# CallerID.net
KiCad netlist of a schematic drawn in Altium Designer
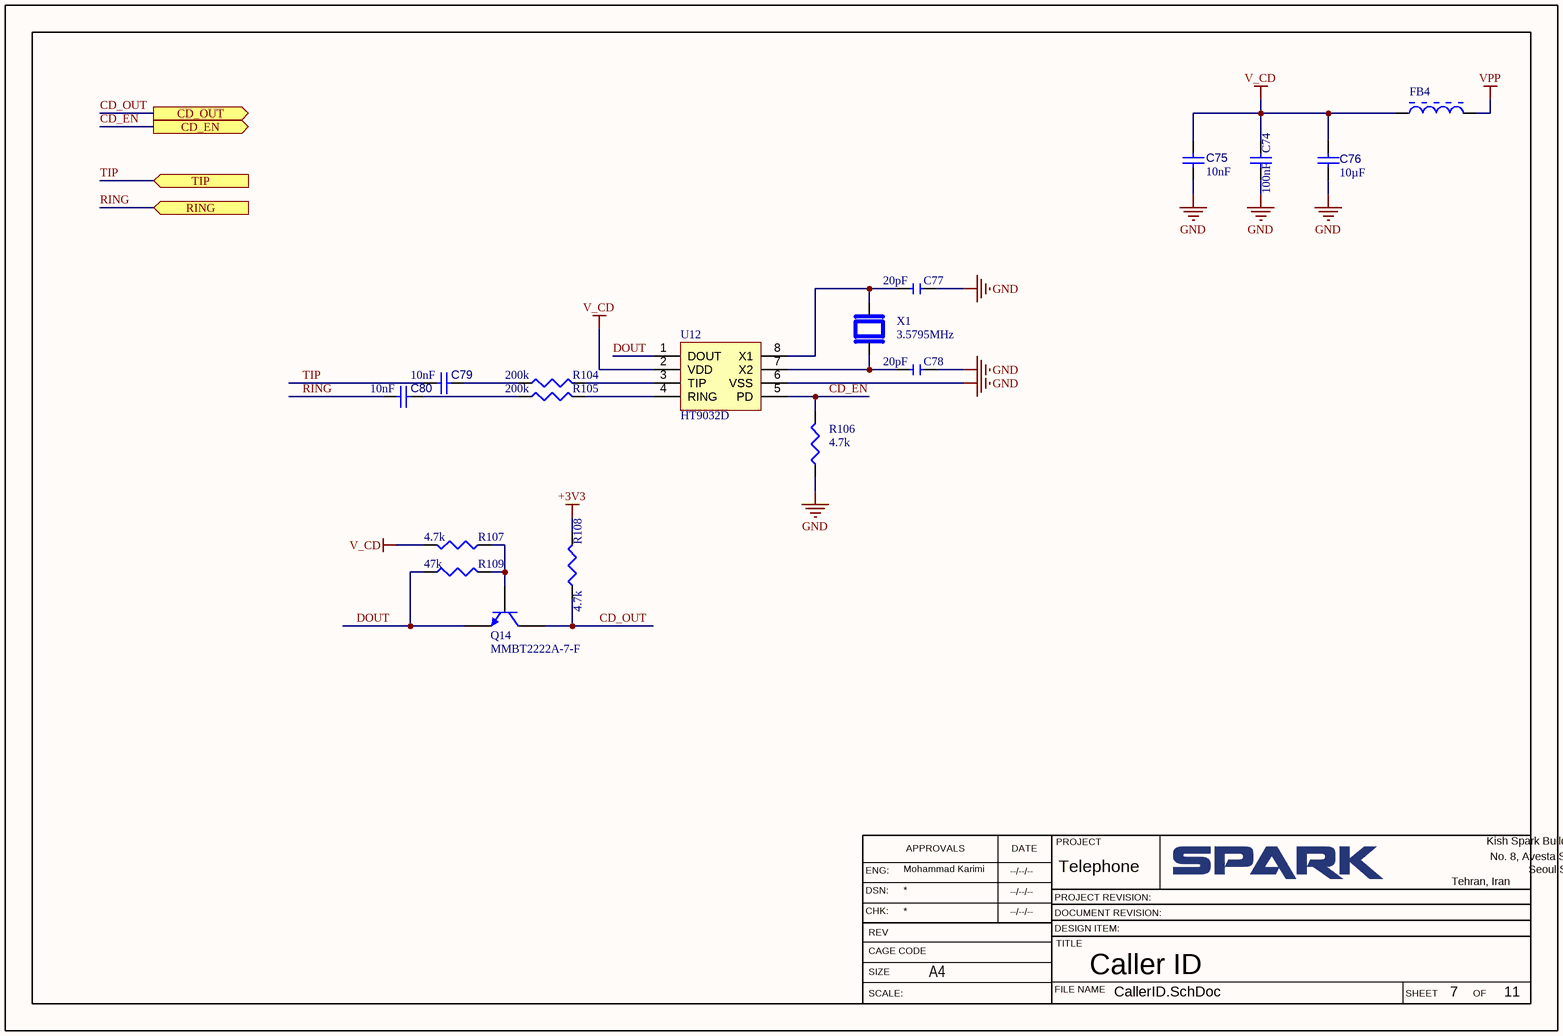
[diagram p0: CallerID.SchDoc]

(export (version "E")
  (design (tool "Eeschema 10.0.6"))
  (components
    (comp (ref "C74")
      (value "100nF")
      (footprint "C0603")
      (description "YAGEO - CC0603KRX7R8BB104 - CERAMIC CAPACITOR, 0.1UF, 25V, X7R, 10%, 0603, FULL REEL")
      (fields
        (field (name "TOLERANCE") "10%")
        (field (name "VOLTAGE") "25V")
        (field (name "SOURCE") "PTZLib.SchLib")
      )
      (libsource (lib "Kish Spark") (part "CAP-NP-2"))
    )
    (comp (ref "C75")
      (value "10nF")
      (footprint "C0603")
      (description "0603 10nF 50 V ±10 % Tolerance X7R Surface Mount Multilayer Ceramic Capacitor")
      (fields (field (name "TOLERANCE") "10%") (field (name "MANUFACTURER") "Kyocera AVX"))
      (libsource (lib "Kish Spark") (part "CAP-NP-2"))
    )
    (comp (ref "C76")
      (value "10µF")
      (footprint "0805")
      (description "Ceramic Capacitor, 10UF, 6.3V, X5R, 10%, 0805, Full Reel")
      (fields
        (field (name "MANUFACTURER") "KEMET")
        (field (name "MANUFACTURER PART NUMBER") "C0805C106K9PACTU")
      )
      (libsource (lib "Kish Spark") (part "CAP-NP-2"))
    )
    (comp (ref "C77")
      (value "20pF")
      (footprint "0805")
      (description "CAP CER 20PF 50V NPO 0805")
      (fields
        (field (name "MANUFACTURER") "Yageo")
        (field (name "MANUFACTURER PART NUMBER") "CC0805JRNPO9BN200")
      )
      (libsource (lib "Kish Spark") (part "CC0805JRNPO9BN200"))
    )
    (comp (ref "C78")
      (value "20pF")
      (footprint "0805")
      (description "CAP CER 20PF 50V NPO 0805")
      (fields
        (field (name "MANUFACTURER") "Yageo")
        (field (name "MANUFACTURER PART NUMBER") "CC0805JRNPO9BN200")
      )
      (libsource (lib "Kish Spark") (part "CC0805JRNPO9BN200"))
    )
    (comp (ref "C79")
      (value "10nF")
      (footprint "C0603")
      (description "0603 10nF 50 V ±10 % Tolerance X7R Surface Mount Multilayer Ceramic Capacitor")
      (fields (field (name "TOLERANCE") "10%") (field (name "MANUFACTURER") "Kyocera AVX"))
      (libsource (lib "Kish Spark") (part "CAP-NP-2"))
    )
    (comp (ref "C80")
      (value "10nF")
      (footprint "C0603")
      (description "0603 10nF 50 V ±10 % Tolerance X7R Surface Mount Multilayer Ceramic Capacitor")
      (fields (field (name "TOLERANCE") "10%") (field (name "MANUFACTURER") "Kyocera AVX"))
      (libsource (lib "Kish Spark") (part "CAP-NP-2"))
    )
    (comp (ref "FB4")
      (value "CMP-006-00051-1")
      (footprint "R0603")
      (description "Ferrite Beads 0603 60ohm")
      (fields (field (name "TOLERANCE") "25%") (field (name "SOURCE") "PTZLib.SchLib"))
      (libsource (lib "Kish Spark") (part "FerriteBead"))
    )
    (comp (ref "Q14")
      (value "MMBT2222A-7-F")
      (footprint "SOT23127P600-8N")
      (description "MMBT2222 Series NPN 350 mW 40 V 600 mA SMT Small Signal Transistor - SOT-23")
      (fields
        (field (name "MANUFACTURER") "Diodes")
        (field (name "VOLTAGE") "40V")
        (field (name "SOURCE") "PTZ.SCHLIB")
      )
      (libsource (lib "Kish Spark") (part "BJT-NPN-EBC-3"))
    )
    (comp (ref "R104")
      (value "200k")
      (footprint "0805")
      (description "Res Thick Film 0805 200K Ohm 1% 1/8W ±100ppm/°C Molded SMD Paper T/R")
      (fields
        (field (name "MANUFACTURER") "Yageo")
        (field (name "MANUFACTURER PART NUMBER") "RC0805FR-07200KL")
      )
      (libsource (lib "Kish Spark") (part "RC0805FR-1018KL (2)"))
    )
    (comp (ref "R105")
      (value "200k")
      (footprint "0805")
      (description "Res Thick Film 0805 200K Ohm 1% 1/8W ±100ppm/°C Molded SMD Paper T/R")
      (fields
        (field (name "MANUFACTURER") "Yageo")
        (field (name "MANUFACTURER PART NUMBER") "RC0805FR-07200KL")
      )
      (libsource (lib "Kish Spark") (part "RC0805FR-1018KL (2)"))
    )
    (comp (ref "R106")
      (value "4.7k")
      (footprint "R0603")
      (description "RES SMD 4.7K OHM 5% 1/10W 0603")
      (fields
        (field (name "TOLERANCE") "5%")
        (field (name "Comment") "KTR03EZPJ472")
        (field (name "SOURCE") "PTZLib.SchLib")
      )
      (libsource (lib "Kish Spark") (part "RN73R1JTTD3302F10"))
    )
    (comp (ref "R107")
      (value "4.7k")
      (footprint "R0603")
      (description "RES SMD 4.7K OHM 5% 1/10W 0603")
      (fields
        (field (name "TOLERANCE") "5%")
        (field (name "Comment") "KTR03EZPJ472")
        (field (name "SOURCE") "PTZLib.SchLib")
      )
      (libsource (lib "Kish Spark") (part "RN73R1JTTD3302F10"))
    )
    (comp (ref "R108")
      (value "4.7k")
      (footprint "R0603")
      (description "RES SMD 4.7K OHM 5% 1/10W 0603")
      (fields
        (field (name "TOLERANCE") "5%")
        (field (name "Comment") "KTR03EZPJ472")
        (field (name "SOURCE") "PTZLib.SchLib")
      )
      (libsource (lib "Kish Spark") (part "RN73R1JTTD3302F10"))
    )
    (comp (ref "R109")
      (value "47k")
      (footprint "0805")
      (description "High Precision-High Stability Chip Resistor Thin Film 0805 47kOhm 1% Paper T/R")
      (fields
        (field (name "MANUFACTURER") "Yageo")
        (field (name "MANUFACTURER PART NUMBER") "RT0805FRE0747KL")
      )
      (libsource (lib "Kish Spark") (part "RC0805FR-1018KL (2)"))
    )
    (comp (ref "U12")
      (value "HT9032D")
      (footprint "SSOIC8")
      (description "SOP-8 Telecommunication Interface ICs ROHS")
      (libsource (lib "Kish Spark") (part "HT9032D"))
    )
    (comp (ref "X1")
      (value "CMP-003-00038-1")
      (footprint "XTAL")
      (description "Crystal 3.579545MHz ±30ppm (Tol) ±50ppm (Stability) 18pF FUND 180Ohm 2-Pin HC-49/US SMD T/R")
      (fields
        (field (name "MANUFACTURER") "Abracon")
        (field (name "MANUFACTURER PART NUMBER") "ABLS-3.579545MHZ-B4-T")
        (field (name "FREQUENCY") "3.5795MHz")
      )
      (libsource (lib "Kish Spark") (part "ABLS-3.579545MHZ-B4-T"))
    )
  )
  (nets
    (net (code "1") (name "+3V3") (class "Default")
      (node (ref "R108") (pin "2") (pinfunction "2_2") (pintype "passive"))
    )
    (net (code "2") (name "/CD_EN") (class "Default")
      (node (ref "R106") (pin "2") (pinfunction "2_2") (pintype "passive"))
      (node (ref "U12") (pin "5") (pinfunction "PD_5") (pintype "passive"))
    )
    (net (code "3") (name "/CD_OUT") (class "Default")
      (node (ref "Q14") (pin "3") (pinfunction "C_3") (pintype "passive"))
      (node (ref "R108") (pin "1") (pinfunction "1_1") (pintype "passive"))
    )
    (net (code "4") (name "/DOUT") (class "Default")
      (node (ref "Q14") (pin "1") (pinfunction "E_1") (pintype "passive"))
      (node (ref "R109") (pin "1") (pinfunction "1_1") (pintype "passive"))
      (node (ref "U12") (pin "1") (pinfunction "DOUT_1") (pintype "passive"))
    )
    (net (code "5") (name "/RING") (class "Default")
      (node (ref "C80") (pin "2") (pinfunction "2_2") (pintype "passive"))
    )
    (net (code "6") (name "/TIP") (class "Default")
      (node (ref "C79") (pin "2") (pinfunction "2_2") (pintype "passive"))
    )
    (net (code "7") (name "GND") (class "Default")
      (node (ref "C74") (pin "2") (pinfunction "2_2") (pintype "passive"))
      (node (ref "C75") (pin "2") (pinfunction "2_2") (pintype "passive"))
      (node (ref "C76") (pin "1") (pinfunction "1_1") (pintype "passive"))
      (node (ref "C77") (pin "1") (pinfunction "1_1") (pintype "passive"))
      (node (ref "C78") (pin "1") (pinfunction "1_1") (pintype "passive"))
      (node (ref "R106") (pin "1") (pinfunction "1_1") (pintype "passive"))
      (node (ref "U12") (pin "6") (pinfunction "VSS_6") (pintype "passive"))
    )
    (net (code "8") (name "Net-(C79-Pad1)") (class "Default")
      (node (ref "C79") (pin "1") (pinfunction "1_1") (pintype "passive"))
      (node (ref "R104") (pin "1") (pinfunction "1_1") (pintype "passive"))
    )
    (net (code "9") (name "Net-(C80-Pad1)") (class "Default")
      (node (ref "C80") (pin "1") (pinfunction "1_1") (pintype "passive"))
      (node (ref "R105") (pin "1") (pinfunction "1_1") (pintype "passive"))
    )
    (net (code "10") (name "Net-(Q14-B)") (class "Default")
      (node (ref "Q14") (pin "2") (pinfunction "B_2") (pintype "passive"))
      (node (ref "R107") (pin "1") (pinfunction "1_1") (pintype "passive"))
      (node (ref "R109") (pin "2") (pinfunction "2_2") (pintype "passive"))
    )
    (net (code "11") (name "Net-(U12-RING)") (class "Default")
      (node (ref "R105") (pin "2") (pinfunction "2_2") (pintype "passive"))
      (node (ref "U12") (pin "4") (pinfunction "RING_4") (pintype "passive"))
    )
    (net (code "12") (name "Net-(U12-TIP)") (class "Default")
      (node (ref "R104") (pin "2") (pinfunction "2_2") (pintype "passive"))
      (node (ref "U12") (pin "3") (pinfunction "TIP_3") (pintype "passive"))
    )
    (net (code "13") (name "Net-(U12-X1)") (class "Default")
      (node (ref "C77") (pin "2") (pinfunction "2_2") (pintype "passive"))
      (node (ref "U12") (pin "8") (pinfunction "X1_8") (pintype "passive"))
      (node (ref "X1") (pin "1") (pinfunction "1_1") (pintype "passive"))
    )
    (net (code "14") (name "Net-(U12-X2)") (class "Default")
      (node (ref "C78") (pin "2") (pinfunction "2_2") (pintype "passive"))
      (node (ref "U12") (pin "7") (pinfunction "X2_7") (pintype "passive"))
      (node (ref "X1") (pin "2") (pinfunction "2_2") (pintype "passive"))
    )
    (net (code "15") (name "VPP") (class "Default")
      (node (ref "FB4") (pin "2") (pinfunction "2_2") (pintype "passive"))
    )
    (net (code "16") (name "V_CD") (class "Default")
      (node (ref "C74") (pin "1") (pinfunction "1_1") (pintype "passive"))
      (node (ref "C75") (pin "1") (pinfunction "1_1") (pintype "passive"))
      (node (ref "C76") (pin "2") (pinfunction "2_2") (pintype "passive"))
      (node (ref "FB4") (pin "1") (pinfunction "1_1") (pintype "passive"))
      (node (ref "R107") (pin "2") (pinfunction "2_2") (pintype "passive"))
      (node (ref "U12") (pin "2") (pinfunction "VDD_2") (pintype "passive"))
    )
  )
)
